# sensor.net
KiCad netlist of a schematic drawn in Altium Designer
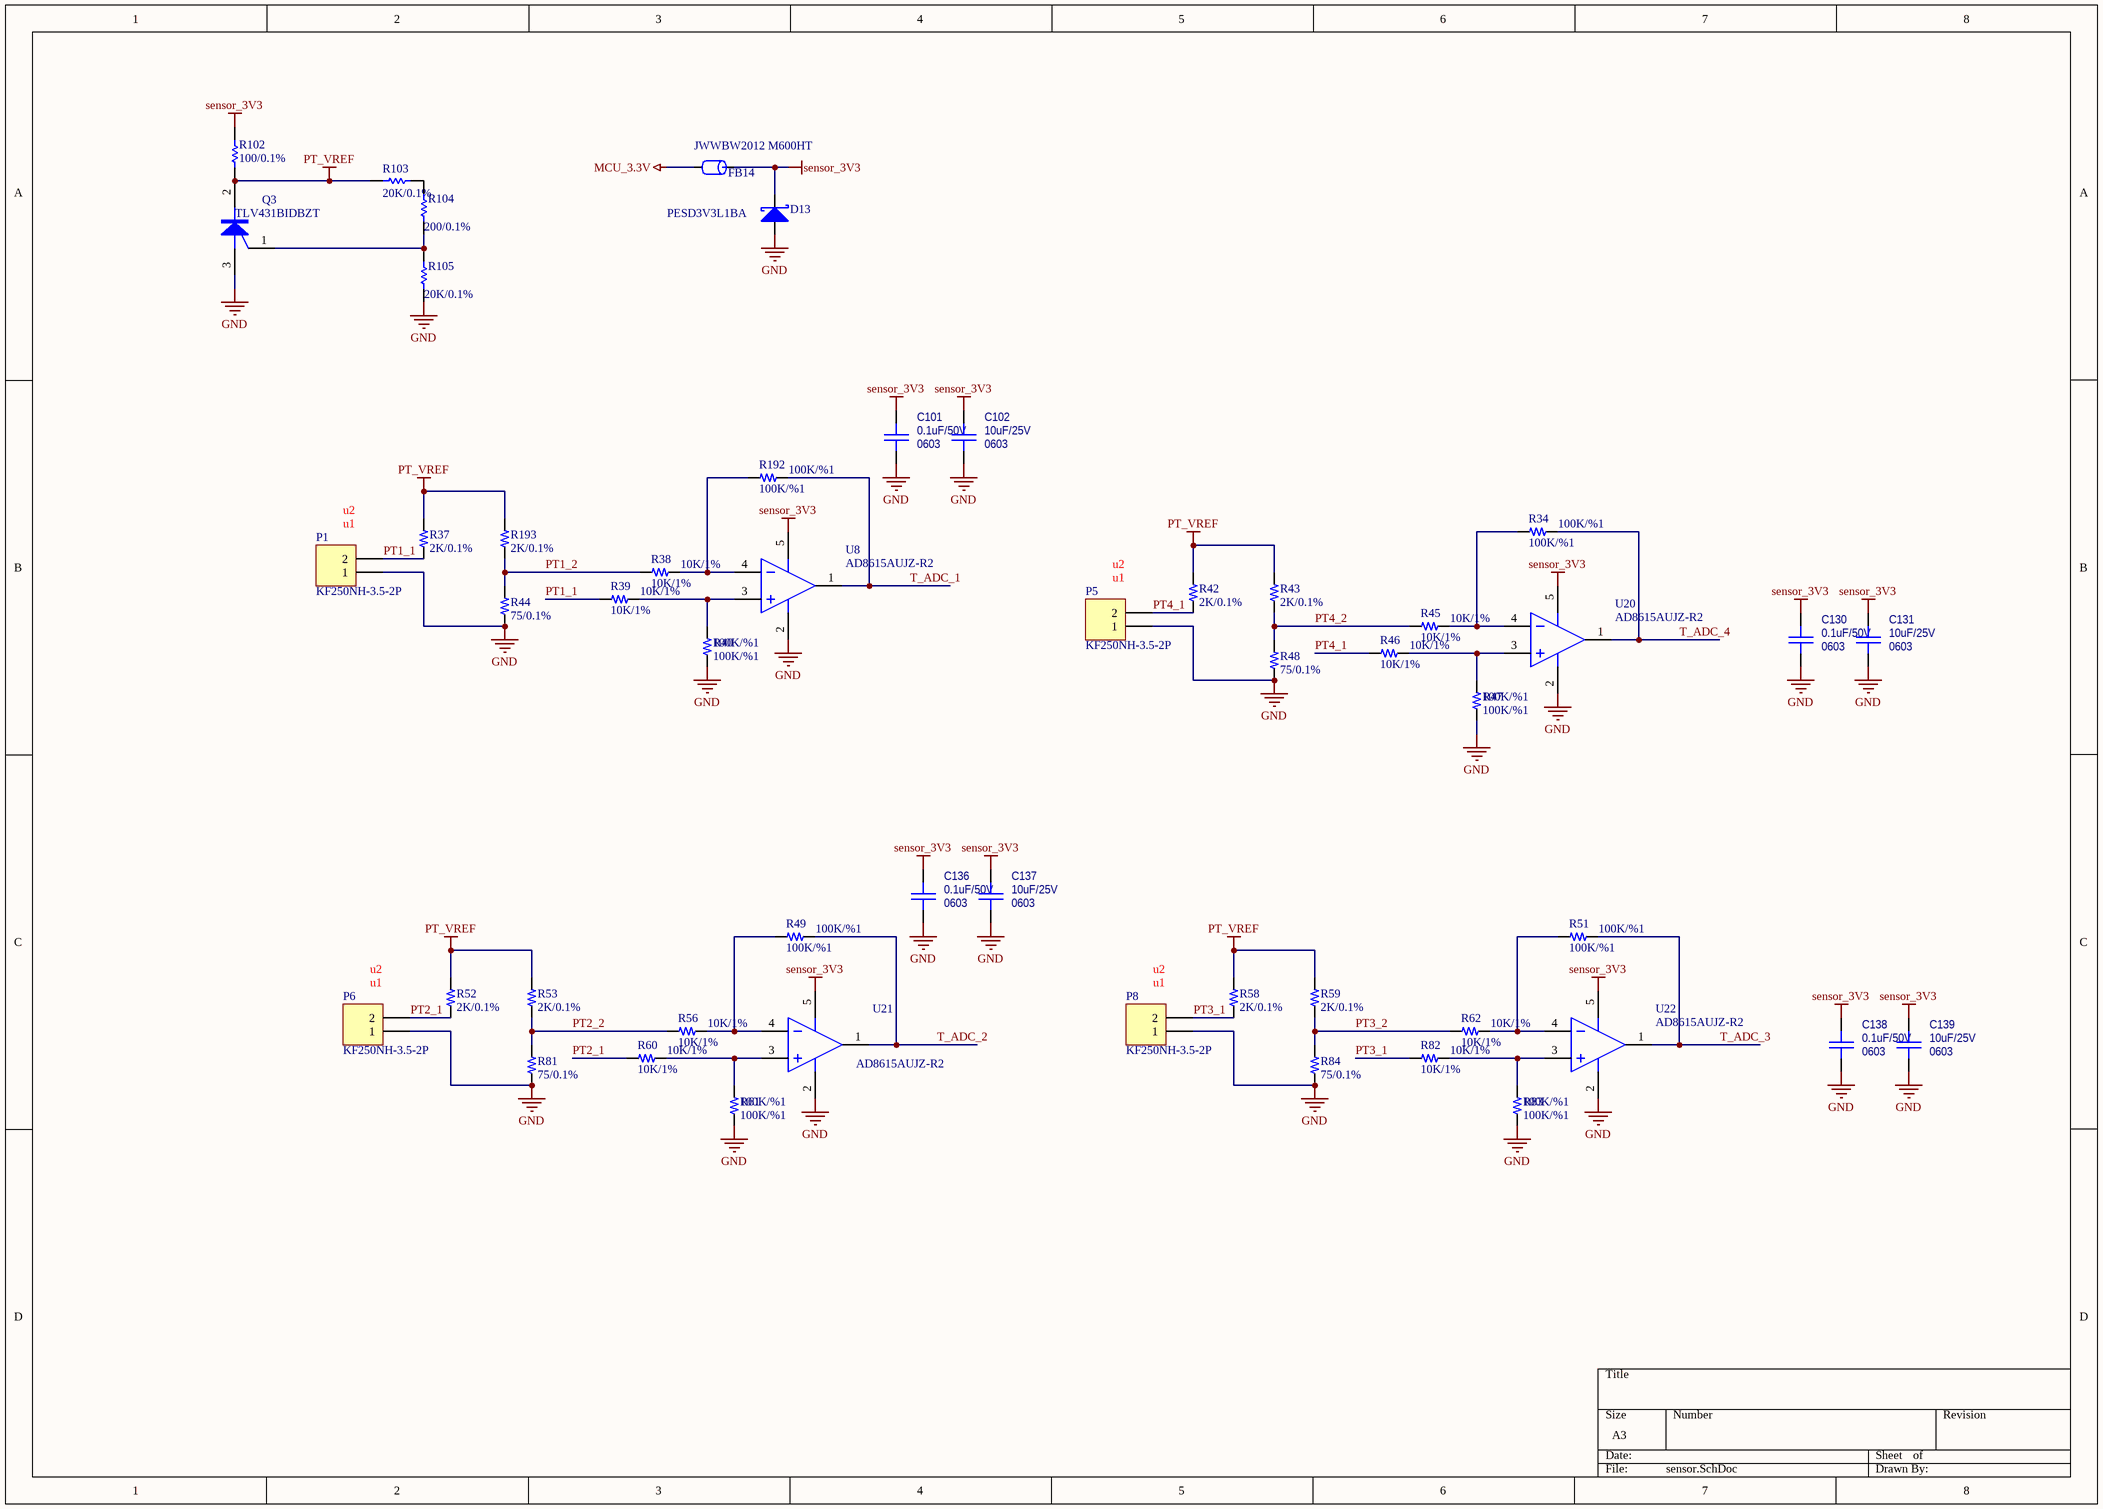
[diagram p0: sensor.SchDoc]

(export (version "E")
  (design (tool "Eeschema 10.0.6"))
  (components
    (comp (ref "C101")
      (value "0.1uF/50V")
      (footprint "CAPC1608X092N_0603")
      (fields
        (field (name "PARTNUMBER") "CC0603KRX7R9BB104")
        (field (name "TOLERANCE") "[tol]")
        (field (name "PACKAGE") "0603")
      )
      (libsource (lib "Karl") (part "Capacitor_0603"))
    )
    (comp (ref "C102")
      (value "10uF/25V")
      (footprint "CAPC1608X092N_0603")
      (fields
        (field (name "PARTNUMBER") "GRM188R61E106MA73D")
        (field (name "TOLERANCE") "[tol]")
        (field (name "PACKAGE") "0603")
      )
      (libsource (lib "Karl") (part "Capacitor_0603"))
    )
    (comp (ref "C130")
      (value "0.1uF/50V")
      (footprint "CAPC1608X092N_0603")
      (fields
        (field (name "PARTNUMBER") "CC0603KRX7R9BB104")
        (field (name "TOLERANCE") "[tol]")
        (field (name "PACKAGE") "0603")
      )
      (libsource (lib "Karl") (part "Capacitor_0603"))
    )
    (comp (ref "C131")
      (value "10uF/25V")
      (footprint "CAPC1608X092N_0603")
      (fields
        (field (name "PARTNUMBER") "GRM188R61E106MA73D")
        (field (name "TOLERANCE") "[tol]")
        (field (name "PACKAGE") "0603")
      )
      (libsource (lib "Karl") (part "Capacitor_0603"))
    )
    (comp (ref "C136")
      (value "0.1uF/50V")
      (footprint "CAPC1608X092N_0603")
      (fields
        (field (name "PARTNUMBER") "CC0603KRX7R9BB104")
        (field (name "TOLERANCE") "[tol]")
        (field (name "PACKAGE") "0603")
      )
      (libsource (lib "Karl") (part "Capacitor_0603"))
    )
    (comp (ref "C137")
      (value "10uF/25V")
      (footprint "CAPC1608X092N_0603")
      (fields
        (field (name "PARTNUMBER") "GRM188R61E106MA73D")
        (field (name "TOLERANCE") "[tol]")
        (field (name "PACKAGE") "0603")
      )
      (libsource (lib "Karl") (part "Capacitor_0603"))
    )
    (comp (ref "C138")
      (value "0.1uF/50V")
      (footprint "CAPC1608X092N_0603")
      (fields
        (field (name "PARTNUMBER") "CC0603KRX7R9BB104")
        (field (name "TOLERANCE") "[tol]")
        (field (name "PACKAGE") "0603")
      )
      (libsource (lib "Karl") (part "Capacitor_0603"))
    )
    (comp (ref "C139")
      (value "10uF/25V")
      (footprint "CAPC1608X092N_0603")
      (fields
        (field (name "PARTNUMBER") "GRM188R61E106MA73D")
        (field (name "TOLERANCE") "[tol]")
        (field (name "PACKAGE") "0603")
      )
      (libsource (lib "Karl") (part "Capacitor_0603"))
    )
    (comp (ref "D13") (value "PESD3V3L1BA") (footprint "SOD323") (libsource (lib "*") (part "DIODE S")))
    (comp (ref "FB14")
      (value "JWWBW2012 M600HT")
      (footprint "0805CZ")
      (fields (field (name "PARTNUMBER") "BLM21PG221SN1D"))
      (libsource (lib "Schlib_20110825") (part "FB"))
    )
    (comp (ref "P1")
      (value "KF250NH-3.5-2P")
      (footprint "KF250NH-3.5-2P")
      (fields (field (name "PUBLISHER") "Altium Limited"))
      (libsource (lib "Miscellaneous Connectors") (part "Header 2"))
    )
    (comp (ref "P5")
      (value "KF250NH-3.5-2P")
      (footprint "KF250NH-3.5-2P")
      (fields (field (name "PUBLISHER") "Altium Limited"))
      (libsource (lib "Miscellaneous Connectors") (part "Header 2"))
    )
    (comp (ref "P6")
      (value "KF250NH-3.5-2P")
      (footprint "KF250NH-3.5-2P")
      (fields (field (name "PUBLISHER") "Altium Limited"))
      (libsource (lib "Miscellaneous Connectors") (part "Header 2"))
    )
    (comp (ref "P8")
      (value "KF250NH-3.5-2P")
      (footprint "KF250NH-3.5-2P")
      (fields (field (name "PUBLISHER") "Altium Limited"))
      (libsource (lib "Miscellaneous Connectors") (part "Header 2"))
    )
    (comp (ref "Q3")
      (value "TLV431BIDBZT")
      (footprint "SOT23-3")
      (description "Programmable Unijunction Transistor")
      (fields (field (name "PARTNUMBER") "TLV431BIDBZR") (field (name "PUBLISHER") "Altium Limited"))
      (libsource (lib "Miscellaneous Devices") (part "PUT"))
    )
    (comp (ref "R34")
      (value "100K/%1")
      (footprint "RESC1608X055N_0603")
      (fields (field (name "ALTIUM_VALUE") "100K/%1") (field (name "PARTNUMBER") "RC0603FR-07100KL"))
      (libsource (lib "JRJ_1") (part "R"))
    )
    (comp (ref "R37") (value "2K/0.1%") (footprint "RESC1608X055N_0603") (libsource (lib "JRJ_1") (part "R")))
    (comp (ref "R38")
      (value "10K/1%")
      (footprint "RESC1608X055N_0603")
      (fields (field (name "ALTIUM_VALUE") "10K/1%") (field (name "PARTNUMBER") "RC0603FR-0710KL"))
      (libsource (lib "JRJ_1") (part "R"))
    )
    (comp (ref "R39")
      (value "10K/1%")
      (footprint "RESC1608X055N_0603")
      (fields (field (name "ALTIUM_VALUE") "10K/1%") (field (name "PARTNUMBER") "RC0603FR-0710KL"))
      (libsource (lib "JRJ_1") (part "R"))
    )
    (comp (ref "R40")
      (value "100K/%1")
      (footprint "RESC1608X055N_0603")
      (fields (field (name "ALTIUM_VALUE") "100K/%1") (field (name "PARTNUMBER") "RC0603FR-07100KL"))
      (libsource (lib "JRJ_1") (part "R"))
    )
    (comp (ref "R42") (value "2K/0.1%") (footprint "RESC1608X055N_0603") (libsource (lib "JRJ_1") (part "R")))
    (comp (ref "R43") (value "2K/0.1%") (footprint "RESC1608X055N_0603") (libsource (lib "JRJ_1") (part "R")))
    (comp (ref "R44")
      (value "75/0.1%")
      (footprint "RESC1608X055N_0603")
      (fields (field (name "PARTNUMBER") "RT0603BRD0775RL"))
      (libsource (lib "JRJ_1") (part "R"))
    )
    (comp (ref "R45")
      (value "10K/1%")
      (footprint "RESC1608X055N_0603")
      (fields (field (name "ALTIUM_VALUE") "10K/1%") (field (name "PARTNUMBER") "RC0603FR-0710KL"))
      (libsource (lib "JRJ_1") (part "R"))
    )
    (comp (ref "R46")
      (value "10K/1%")
      (footprint "RESC1608X055N_0603")
      (fields (field (name "ALTIUM_VALUE") "10K/1%") (field (name "PARTNUMBER") "RC0603FR-0710KL"))
      (libsource (lib "JRJ_1") (part "R"))
    )
    (comp (ref "R47")
      (value "100K/%1")
      (footprint "RESC1608X055N_0603")
      (fields (field (name "ALTIUM_VALUE") "100K/%1") (field (name "PARTNUMBER") "RC0603FR-07100KL"))
      (libsource (lib "JRJ_1") (part "R"))
    )
    (comp (ref "R48")
      (value "75/0.1%")
      (footprint "RESC1608X055N_0603")
      (fields (field (name "PARTNUMBER") "RT0603BRD0775RL"))
      (libsource (lib "JRJ_1") (part "R"))
    )
    (comp (ref "R49")
      (value "100K/%1")
      (footprint "RESC1608X055N_0603")
      (fields (field (name "ALTIUM_VALUE") "100K/%1") (field (name "PARTNUMBER") "RC0603FR-07100KL"))
      (libsource (lib "JRJ_1") (part "R"))
    )
    (comp (ref "R51")
      (value "100K/%1")
      (footprint "RESC1608X055N_0603")
      (fields (field (name "ALTIUM_VALUE") "100K/%1") (field (name "PARTNUMBER") "RC0603FR-07100KL"))
      (libsource (lib "JRJ_1") (part "R"))
    )
    (comp (ref "R52") (value "2K/0.1%") (footprint "RESC1608X055N_0603") (libsource (lib "JRJ_1") (part "R")))
    (comp (ref "R53") (value "2K/0.1%") (footprint "RESC1608X055N_0603") (libsource (lib "JRJ_1") (part "R")))
    (comp (ref "R56")
      (value "10K/1%")
      (footprint "RESC1608X055N_0603")
      (fields (field (name "ALTIUM_VALUE") "10K/1%") (field (name "PARTNUMBER") "RC0603FR-0710KL"))
      (libsource (lib "JRJ_1") (part "R"))
    )
    (comp (ref "R58") (value "2K/0.1%") (footprint "RESC1608X055N_0603") (libsource (lib "JRJ_1") (part "R")))
    (comp (ref "R59") (value "2K/0.1%") (footprint "RESC1608X055N_0603") (libsource (lib "JRJ_1") (part "R")))
    (comp (ref "R60")
      (value "10K/1%")
      (footprint "RESC1608X055N_0603")
      (fields (field (name "ALTIUM_VALUE") "10K/1%") (field (name "PARTNUMBER") "RC0603FR-0710KL"))
      (libsource (lib "JRJ_1") (part "R"))
    )
    (comp (ref "R61")
      (value "100K/%1")
      (footprint "RESC1608X055N_0603")
      (fields (field (name "ALTIUM_VALUE") "100K/%1") (field (name "PARTNUMBER") "RC0603FR-07100KL"))
      (libsource (lib "JRJ_1") (part "R"))
    )
    (comp (ref "R62")
      (value "10K/1%")
      (footprint "RESC1608X055N_0603")
      (fields (field (name "ALTIUM_VALUE") "10K/1%") (field (name "PARTNUMBER") "RC0603FR-0710KL"))
      (libsource (lib "JRJ_1") (part "R"))
    )
    (comp (ref "R81")
      (value "75/0.1%")
      (footprint "RESC1608X055N_0603")
      (fields (field (name "PARTNUMBER") "RT0603BRD0775RL"))
      (libsource (lib "JRJ_1") (part "R"))
    )
    (comp (ref "R82")
      (value "10K/1%")
      (footprint "RESC1608X055N_0603")
      (fields (field (name "ALTIUM_VALUE") "10K/1%") (field (name "PARTNUMBER") "RC0603FR-0710KL"))
      (libsource (lib "JRJ_1") (part "R"))
    )
    (comp (ref "R83")
      (value "100K/%1")
      (footprint "RESC1608X055N_0603")
      (fields (field (name "ALTIUM_VALUE") "100K/%1") (field (name "PARTNUMBER") "RC0603FR-07100KL"))
      (libsource (lib "JRJ_1") (part "R"))
    )
    (comp (ref "R84")
      (value "75/0.1%")
      (footprint "RESC1608X055N_0603")
      (fields (field (name "PARTNUMBER") "RT0603BRD0775RL"))
      (libsource (lib "JRJ_1") (part "R"))
    )
    (comp (ref "R102")
      (value "100/0.1%")
      (footprint "RESC1608X055N_0603")
      (description "Resistor")
      (fields (field (name "PARTNUMBER") "RT0603BRD07100RL") (field (name "PUBLISHER") "Altium Limited"))
      (libsource (lib "Miscellaneous Devices") (part "Res1"))
    )
    (comp (ref "R103")
      (value "20K/0.1%")
      (footprint "RESC1608X055N_0603")
      (description "Resistor")
      (fields (field (name "PARTNUMBER") "RT0603BRD0720KL") (field (name "PUBLISHER") "Altium Limited"))
      (libsource (lib "Miscellaneous Devices") (part "Res1"))
    )
    (comp (ref "R104")
      (value "200/0.1%")
      (footprint "RESC1608X055N_0603")
      (description "Resistor")
      (fields (field (name "PARTNUMBER") "RT0603BRD07200RL") (field (name "PUBLISHER") "Altium Limited"))
      (libsource (lib "Miscellaneous Devices") (part "Res1"))
    )
    (comp (ref "R105")
      (value "20K/0.1%")
      (footprint "RESC1608X055N_0603")
      (description "Resistor")
      (fields (field (name "PARTNUMBER") "RT0603BRD0720KL") (field (name "PUBLISHER") "Altium Limited"))
      (libsource (lib "Miscellaneous Devices") (part "Res1"))
    )
    (comp (ref "R192")
      (value "100K/%1")
      (footprint "RESC1608X055N_0603")
      (fields (field (name "ALTIUM_VALUE") "100K/%1") (field (name "PARTNUMBER") "RC0603FR-07100KL"))
      (libsource (lib "JRJ_1") (part "R"))
    )
    (comp (ref "R193")
      (value "2K/0.1%")
      (footprint "RESC1608X055N_0603")
      (libsource (lib "JRJ_1") (part "R"))
    )
    (comp (ref "U8")
      (value "AD8615AUJZ-R2")
      (footprint "sot-23-5")
      (libsource (lib "Schlib_20110825") (part "AD8615"))
    )
    (comp (ref "U20")
      (value "AD8615AUJZ-R2")
      (footprint "sot-23-5")
      (libsource (lib "Schlib_20110825") (part "AD8615"))
    )
    (comp (ref "U21")
      (value "AD8615AUJZ-R2")
      (footprint "sot-23-5")
      (libsource (lib "Schlib_20110825") (part "AD8615"))
    )
    (comp (ref "U22")
      (value "AD8615AUJZ-R2")
      (footprint "sot-23-5")
      (libsource (lib "Schlib_20110825") (part "AD8615"))
    )
  )
  (nets
    (net (code "1") (name "/PT1_1") (class "Default")
      (node (ref "P1") (pin "2") (pinfunction "2_2") (pintype "passive"))
      (node (ref "R37") (pin "1") (pintype "passive"))
      (node (ref "R39") (pin "2") (pintype "passive"))
    )
    (net (code "2") (name "/PT1_2") (class "Default")
      (node (ref "R193") (pin "1") (pintype "passive"))
      (node (ref "R38") (pin "2") (pintype "passive"))
      (node (ref "R44") (pin "2") (pintype "passive"))
    )
    (net (code "3") (name "/PT2_1") (class "Default")
      (node (ref "P6") (pin "2") (pinfunction "2_2") (pintype "passive"))
      (node (ref "R52") (pin "1") (pintype "passive"))
      (node (ref "R60") (pin "2") (pintype "passive"))
    )
    (net (code "4") (name "/PT2_2") (class "Default")
      (node (ref "R53") (pin "1") (pintype "passive"))
      (node (ref "R56") (pin "2") (pintype "passive"))
      (node (ref "R81") (pin "2") (pintype "passive"))
    )
    (net (code "5") (name "/PT3_1") (class "Default")
      (node (ref "P8") (pin "2") (pinfunction "2_2") (pintype "passive"))
      (node (ref "R58") (pin "1") (pintype "passive"))
      (node (ref "R82") (pin "2") (pintype "passive"))
    )
    (net (code "6") (name "/PT3_2") (class "Default")
      (node (ref "R59") (pin "1") (pintype "passive"))
      (node (ref "R62") (pin "2") (pintype "passive"))
      (node (ref "R84") (pin "2") (pintype "passive"))
    )
    (net (code "7") (name "/PT4_1") (class "Default")
      (node (ref "P5") (pin "2") (pinfunction "2_2") (pintype "passive"))
      (node (ref "R42") (pin "1") (pintype "passive"))
      (node (ref "R46") (pin "2") (pintype "passive"))
    )
    (net (code "8") (name "/PT4_2") (class "Default")
      (node (ref "R43") (pin "1") (pintype "passive"))
      (node (ref "R45") (pin "2") (pintype "passive"))
      (node (ref "R48") (pin "2") (pintype "passive"))
    )
    (net (code "9") (name "/T_ADC_1") (class "Default")
      (node (ref "R192") (pin "1") (pintype "passive"))
      (node (ref "U8") (pin "1") (pinfunction "OS_NUL_1") (pintype "passive"))
    )
    (net (code "10") (name "/T_ADC_2") (class "Default")
      (node (ref "R49") (pin "1") (pintype "passive"))
      (node (ref "U21") (pin "1") (pinfunction "OS_NUL_1") (pintype "passive"))
    )
    (net (code "11") (name "/T_ADC_3") (class "Default")
      (node (ref "R51") (pin "1") (pintype "passive"))
      (node (ref "U22") (pin "1") (pinfunction "OS_NUL_1") (pintype "passive"))
    )
    (net (code "12") (name "/T_ADC_4") (class "Default")
      (node (ref "R34") (pin "1") (pintype "passive"))
      (node (ref "U20") (pin "1") (pinfunction "OS_NUL_1") (pintype "passive"))
    )
    (net (code "13") (name "GND") (class "Default")
      (node (ref "C101") (pin "2") (pinfunction "2_2") (pintype "passive"))
      (node (ref "C102") (pin "2") (pinfunction "2_2") (pintype "passive"))
      (node (ref "C130") (pin "2") (pinfunction "2_2") (pintype "passive"))
      (node (ref "C131") (pin "2") (pinfunction "2_2") (pintype "passive"))
      (node (ref "C136") (pin "2") (pinfunction "2_2") (pintype "passive"))
      (node (ref "C137") (pin "2") (pinfunction "2_2") (pintype "passive"))
      (node (ref "C138") (pin "2") (pinfunction "2_2") (pintype "passive"))
      (node (ref "C139") (pin "2") (pinfunction "2_2") (pintype "passive"))
      (node (ref "D13") (pin "1") (pinfunction "A_1") (pintype "passive"))
      (node (ref "P1") (pin "1") (pinfunction "1_1") (pintype "passive"))
      (node (ref "P5") (pin "1") (pinfunction "1_1") (pintype "passive"))
      (node (ref "P6") (pin "1") (pinfunction "1_1") (pintype "passive"))
      (node (ref "P8") (pin "1") (pinfunction "1_1") (pintype "passive"))
      (node (ref "Q3") (pin "3") (pinfunction "A_3") (pintype "passive"))
      (node (ref "R105") (pin "2") (pinfunction "2_2") (pintype "passive"))
      (node (ref "R40") (pin "2") (pintype "passive"))
      (node (ref "R44") (pin "1") (pintype "passive"))
      (node (ref "R47") (pin "2") (pintype "passive"))
      (node (ref "R48") (pin "1") (pintype "passive"))
      (node (ref "R61") (pin "2") (pintype "passive"))
      (node (ref "R81") (pin "1") (pintype "passive"))
      (node (ref "R83") (pin "2") (pintype "passive"))
      (node (ref "R84") (pin "1") (pintype "passive"))
      (node (ref "U20") (pin "2") (pinfunction "G_2") (pintype "power_in"))
      (node (ref "U21") (pin "2") (pinfunction "G_2") (pintype "power_in"))
      (node (ref "U22") (pin "2") (pinfunction "G_2") (pintype "power_in"))
      (node (ref "U8") (pin "2") (pinfunction "G_2") (pintype "power_in"))
    )
    (net (code "14") (name "MCU_3.3V") (class "Default") (node (ref "FB14") (pin "2") (pintype "passive")))
    (net (code "15") (name "Net-(Q3-G)") (class "Default")
      (node (ref "Q3") (pin "1") (pinfunction "G_1") (pintype "passive"))
      (node (ref "R104") (pin "2") (pinfunction "2_2") (pintype "passive"))
      (node (ref "R105") (pin "1") (pinfunction "1_1") (pintype "passive"))
    )
    (net (code "16") (name "Net-(R103-Pad2)") (class "Default")
      (node (ref "R103") (pin "2") (pinfunction "2_2") (pintype "passive"))
      (node (ref "R104") (pin "1") (pinfunction "1_1") (pintype "passive"))
    )
    (net (code "17") (name "Net-(U8-V+)") (class "Default")
      (node (ref "R39") (pin "1") (pintype "passive"))
      (node (ref "R40") (pin "1") (pintype "passive"))
      (node (ref "U8") (pin "3") (pinfunction "V+_3") (pintype "power_in"))
    )
    (net (code "18") (name "Net-(U8-V-)") (class "Default")
      (node (ref "R192") (pin "2") (pintype "passive"))
      (node (ref "R38") (pin "1") (pintype "passive"))
      (node (ref "U8") (pin "4") (pinfunction "V-_4") (pintype "power_in"))
    )
    (net (code "19") (name "Net-(U20-V+)") (class "Default")
      (node (ref "R46") (pin "1") (pintype "passive"))
      (node (ref "R47") (pin "1") (pintype "passive"))
      (node (ref "U20") (pin "3") (pinfunction "V+_3") (pintype "power_in"))
    )
    (net (code "20") (name "Net-(U20-V-)") (class "Default")
      (node (ref "R34") (pin "2") (pintype "passive"))
      (node (ref "R45") (pin "1") (pintype "passive"))
      (node (ref "U20") (pin "4") (pinfunction "V-_4") (pintype "power_in"))
    )
    (net (code "21") (name "Net-(U21-V+)") (class "Default")
      (node (ref "R60") (pin "1") (pintype "passive"))
      (node (ref "R61") (pin "1") (pintype "passive"))
      (node (ref "U21") (pin "3") (pinfunction "V+_3") (pintype "power_in"))
    )
    (net (code "22") (name "Net-(U21-V-)") (class "Default")
      (node (ref "R49") (pin "2") (pintype "passive"))
      (node (ref "R56") (pin "1") (pintype "passive"))
      (node (ref "U21") (pin "4") (pinfunction "V-_4") (pintype "power_in"))
    )
    (net (code "23") (name "Net-(U22-V+)") (class "Default")
      (node (ref "R82") (pin "1") (pintype "passive"))
      (node (ref "R83") (pin "1") (pintype "passive"))
      (node (ref "U22") (pin "3") (pinfunction "V+_3") (pintype "power_in"))
    )
    (net (code "24") (name "Net-(U22-V-)") (class "Default")
      (node (ref "R51") (pin "2") (pintype "passive"))
      (node (ref "R62") (pin "1") (pintype "passive"))
      (node (ref "U22") (pin "4") (pinfunction "V-_4") (pintype "power_in"))
    )
    (net (code "25") (name "PT_VREF") (class "Default")
      (node (ref "Q3") (pin "2") (pinfunction "K_2") (pintype "passive"))
      (node (ref "R102") (pin "2") (pinfunction "2_2") (pintype "passive"))
      (node (ref "R103") (pin "1") (pinfunction "1_1") (pintype "passive"))
      (node (ref "R193") (pin "2") (pintype "passive"))
      (node (ref "R37") (pin "2") (pintype "passive"))
      (node (ref "R42") (pin "2") (pintype "passive"))
      (node (ref "R43") (pin "2") (pintype "passive"))
      (node (ref "R52") (pin "2") (pintype "passive"))
      (node (ref "R53") (pin "2") (pintype "passive"))
      (node (ref "R58") (pin "2") (pintype "passive"))
      (node (ref "R59") (pin "2") (pintype "passive"))
    )
    (net (code "26") (name "sensor_3V3") (class "Default")
      (node (ref "C101") (pin "1") (pinfunction "1_1") (pintype "passive"))
      (node (ref "C102") (pin "1") (pinfunction "1_1") (pintype "passive"))
      (node (ref "C130") (pin "1") (pinfunction "1_1") (pintype "passive"))
      (node (ref "C131") (pin "1") (pinfunction "1_1") (pintype "passive"))
      (node (ref "C136") (pin "1") (pinfunction "1_1") (pintype "passive"))
      (node (ref "C137") (pin "1") (pinfunction "1_1") (pintype "passive"))
      (node (ref "C138") (pin "1") (pinfunction "1_1") (pintype "passive"))
      (node (ref "C139") (pin "1") (pinfunction "1_1") (pintype "passive"))
      (node (ref "D13") (pin "2") (pinfunction "K_2") (pintype "passive"))
      (node (ref "FB14") (pin "1") (pintype "passive"))
      (node (ref "R102") (pin "1") (pinfunction "1_1") (pintype "passive"))
      (node (ref "U20") (pin "5") (pinfunction "VCC_5") (pintype "passive"))
      (node (ref "U21") (pin "5") (pinfunction "VCC_5") (pintype "passive"))
      (node (ref "U22") (pin "5") (pinfunction "VCC_5") (pintype "passive"))
      (node (ref "U8") (pin "5") (pinfunction "VCC_5") (pintype "passive"))
    )
  )
)
